# Overview.net
KiCad netlist of a schematic drawn in Altium Designer
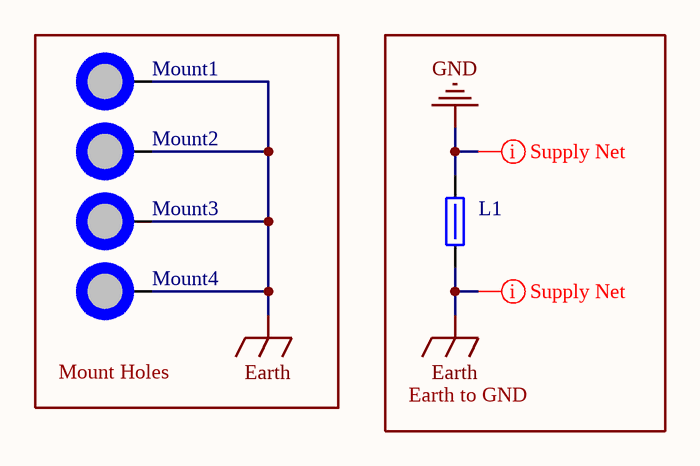
[diagram p0: Overview.SchDoc]

(export (version "E")
  (design (tool "Eeschema 10.0.6"))
  (components
    (comp (ref "L1")
      (value "742792040")
      (footprint "[Ferrite] SMD Bead 0805 (2)")
      (libsource (lib "RADM Components") (part "[Ferrite] SMD Ferrite Bead (2)"))
    )
    (comp (ref "Mount1")
      (value "M3 Mount Hole")
      (footprint "[Mount] M3 Mount Hole")
      (description "Place at least 4.5mm from board edge. Plated.")
      (libsource (lib "Mounts, Pads, Vias") (part "[Mount] M3 Mount Hole"))
    )
    (comp (ref "Mount2")
      (value "M3 Mount Hole")
      (footprint "[Mount] M3 Mount Hole")
      (description "Place at least 4.5mm from board edge. Plated.")
      (libsource (lib "Mounts, Pads, Vias") (part "[Mount] M3 Mount Hole"))
    )
    (comp (ref "Mount3")
      (value "M3 Mount Hole")
      (footprint "[Mount] M3 Mount Hole")
      (description "Place at least 4.5mm from board edge. Plated.")
      (libsource (lib "Mounts, Pads, Vias") (part "[Mount] M3 Mount Hole"))
    )
    (comp (ref "Mount4")
      (value "M3 Mount Hole")
      (footprint "[Mount] M3 Mount Hole")
      (description "Place at least 4.5mm from board edge. Plated.")
      (libsource (lib "Mounts, Pads, Vias") (part "[Mount] M3 Mount Hole"))
    )
  )
  (nets
    (net (code "1") (name "Earth") (class "Default")
      (node (ref "L1") (pin "1") (pinfunction "1_1") (pintype "passive"))
      (node (ref "Mount1") (pin "1") (pintype "power_in"))
      (node (ref "Mount2") (pin "1") (pintype "power_in"))
      (node (ref "Mount3") (pin "1") (pintype "power_in"))
      (node (ref "Mount4") (pin "1") (pintype "power_in"))
    )
    (net (code "2") (name "GND") (class "Default")
      (node (ref "L1") (pin "2") (pinfunction "2_2") (pintype "passive"))
    )
  )
)
